# TestV1_0.net
KiCad netlist of a schematic drawn in EAGLE
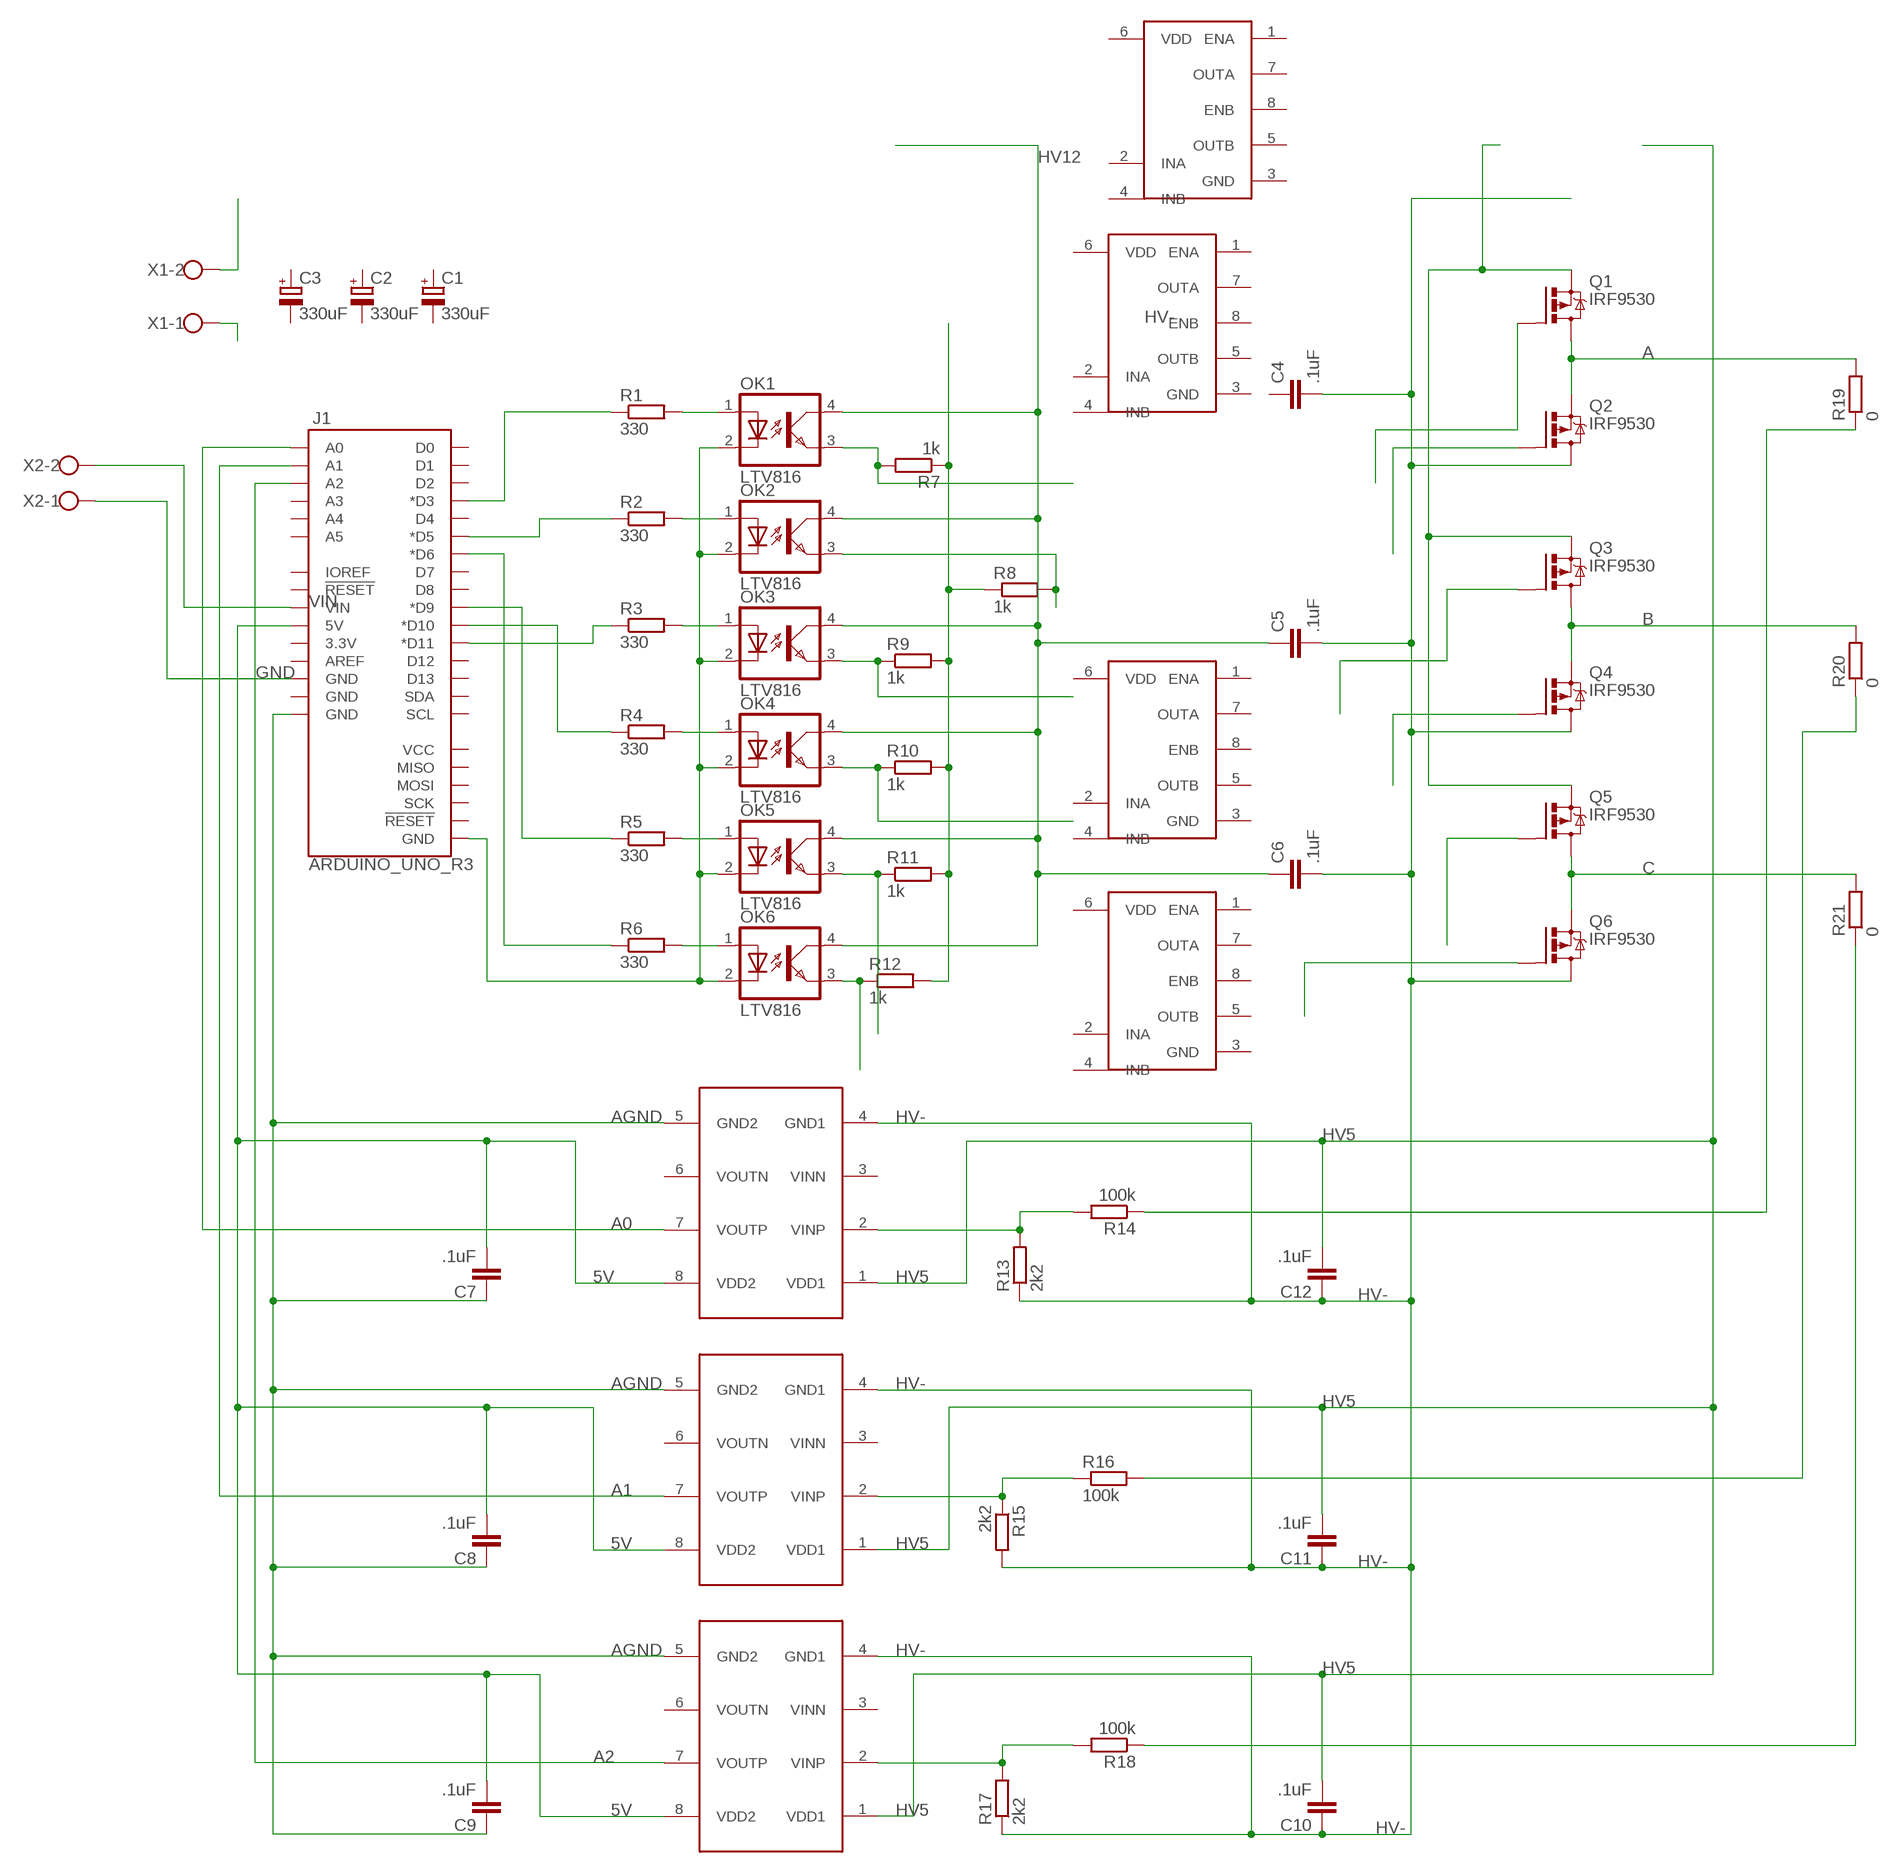
[diagram p0: schematic, sheet 1]

(export (version "E")
  (design (tool "Eeschema 10.0.6"))
  (components
    (comp (ref "C1")
      (value "330uF")
      (footprint "eagle-import:E5-13")
      (libsource (lib "eagle-import") (part "CPOL-EUE5-13"))
    )
    (comp (ref "C2")
      (value "330uF")
      (footprint "eagle-import:E5-13")
      (libsource (lib "eagle-import") (part "CPOL-EUE5-13"))
    )
    (comp (ref "C3")
      (value "330uF")
      (footprint "eagle-import:E5-13")
      (libsource (lib "eagle-import") (part "CPOL-EUE5-13"))
    )
    (comp (ref "C4")
      (value ".1uF")
      (footprint "eagle-import:C0603")
      (libsource (lib "eagle-import") (part "C-EUC0603"))
    )
    (comp (ref "C5")
      (value ".1uF")
      (footprint "eagle-import:C0603")
      (libsource (lib "eagle-import") (part "C-EUC0603"))
    )
    (comp (ref "C6")
      (value ".1uF")
      (footprint "eagle-import:C0603")
      (libsource (lib "eagle-import") (part "C-EUC0603"))
    )
    (comp (ref "C7")
      (value ".1uF")
      (footprint "eagle-import:C0603")
      (libsource (lib "eagle-import") (part "C-EUC0603"))
    )
    (comp (ref "C8")
      (value ".1uF")
      (footprint "eagle-import:C0603")
      (libsource (lib "eagle-import") (part "C-EUC0603"))
    )
    (comp (ref "C9")
      (value ".1uF")
      (footprint "eagle-import:C0603")
      (libsource (lib "eagle-import") (part "C-EUC0603"))
    )
    (comp (ref "C10")
      (value ".1uF")
      (footprint "eagle-import:C0603")
      (libsource (lib "eagle-import") (part "C-EUC0603"))
    )
    (comp (ref "C11")
      (value ".1uF")
      (footprint "eagle-import:C0603")
      (libsource (lib "eagle-import") (part "C-EUC0603"))
    )
    (comp (ref "C12")
      (value ".1uF")
      (footprint "eagle-import:C0603")
      (libsource (lib "eagle-import") (part "C-EUC0603"))
    )
    (comp (ref "J1")
      (value "ARDUINO_UNO_R3")
      (footprint "eagle-import:ARDUINO_R3")
      (libsource (lib "eagle-import") (part "ARDUINO_UNO_R3"))
    )
    (comp (ref "MAX17604_A")
      (value "MAX17604")
      (footprint "eagle-import:SO08")
      (libsource (lib "eagle-import") (part "MAX17604"))
    )
    (comp (ref "MAX17604_B")
      (value "MAX17604")
      (footprint "eagle-import:SO08")
      (libsource (lib "eagle-import") (part "MAX17604"))
    )
    (comp (ref "MAX17604_C")
      (value "MAX17604")
      (footprint "eagle-import:SO08")
      (libsource (lib "eagle-import") (part "MAX17604"))
    )
    (comp (ref "MAX17604_D")
      (value "MAX17604")
      (footprint "eagle-import:SO08")
      (libsource (lib "eagle-import") (part "MAX17604"))
    )
    (comp (ref "OK1")
      (value "LTV816")
      (footprint "eagle-import:DIL04")
      (libsource (lib "eagle-import") (part "LTV816"))
    )
    (comp (ref "OK2")
      (value "LTV816")
      (footprint "eagle-import:DIL04")
      (libsource (lib "eagle-import") (part "LTV816"))
    )
    (comp (ref "OK3")
      (value "LTV816")
      (footprint "eagle-import:DIL04")
      (libsource (lib "eagle-import") (part "LTV816"))
    )
    (comp (ref "OK4")
      (value "LTV816")
      (footprint "eagle-import:DIL04")
      (libsource (lib "eagle-import") (part "LTV816"))
    )
    (comp (ref "OK5")
      (value "LTV816")
      (footprint "eagle-import:DIL04")
      (libsource (lib "eagle-import") (part "LTV816"))
    )
    (comp (ref "OK6")
      (value "LTV816")
      (footprint "eagle-import:DIL04")
      (libsource (lib "eagle-import") (part "LTV816"))
    )
    (comp (ref "Q1")
      (value "IRF9530")
      (footprint "eagle-import:TO220BV")
      (libsource (lib "eagle-import") (part "IRF9530"))
    )
    (comp (ref "Q2")
      (value "IRF9530")
      (footprint "eagle-import:TO220BV")
      (libsource (lib "eagle-import") (part "IRF9530"))
    )
    (comp (ref "Q3")
      (value "IRF9530")
      (footprint "eagle-import:TO220BV")
      (libsource (lib "eagle-import") (part "IRF9530"))
    )
    (comp (ref "Q4")
      (value "IRF9530")
      (footprint "eagle-import:TO220BV")
      (libsource (lib "eagle-import") (part "IRF9530"))
    )
    (comp (ref "Q5")
      (value "IRF9530")
      (footprint "eagle-import:TO220BV")
      (libsource (lib "eagle-import") (part "IRF9530"))
    )
    (comp (ref "Q6")
      (value "IRF9530")
      (footprint "eagle-import:TO220BV")
      (libsource (lib "eagle-import") (part "IRF9530"))
    )
    (comp (ref "R1")
      (value "330")
      (footprint "eagle-import:R0603")
      (libsource (lib "eagle-import") (part "eagle-ltspice_217_RR0603"))
    )
    (comp (ref "R2")
      (value "330")
      (footprint "eagle-import:R0603")
      (libsource (lib "eagle-import") (part "eagle-ltspice_217_RR0603"))
    )
    (comp (ref "R3")
      (value "330")
      (footprint "eagle-import:R0603")
      (libsource (lib "eagle-import") (part "eagle-ltspice_217_RR0603"))
    )
    (comp (ref "R4")
      (value "330")
      (footprint "eagle-import:R0603")
      (libsource (lib "eagle-import") (part "eagle-ltspice_217_RR0603"))
    )
    (comp (ref "R5")
      (value "330")
      (footprint "eagle-import:R0603")
      (libsource (lib "eagle-import") (part "eagle-ltspice_217_RR0603"))
    )
    (comp (ref "R6")
      (value "330")
      (footprint "eagle-import:R0603")
      (libsource (lib "eagle-import") (part "eagle-ltspice_217_RR0603"))
    )
    (comp (ref "R7")
      (value "1k")
      (footprint "eagle-import:R0603")
      (libsource (lib "eagle-import") (part "eagle-ltspice_217_RR0603"))
    )
    (comp (ref "R8")
      (value "1k")
      (footprint "eagle-import:R0603")
      (libsource (lib "eagle-import") (part "eagle-ltspice_217_RR0603"))
    )
    (comp (ref "R9")
      (value "1k")
      (footprint "eagle-import:R0603")
      (libsource (lib "eagle-import") (part "eagle-ltspice_217_RR0603"))
    )
    (comp (ref "R10")
      (value "1k")
      (footprint "eagle-import:R0603")
      (libsource (lib "eagle-import") (part "eagle-ltspice_217_RR0603"))
    )
    (comp (ref "R11")
      (value "1k")
      (footprint "eagle-import:R0603")
      (libsource (lib "eagle-import") (part "eagle-ltspice_217_RR0603"))
    )
    (comp (ref "R12")
      (value "1k")
      (footprint "eagle-import:R0603")
      (libsource (lib "eagle-import") (part "eagle-ltspice_217_RR0603"))
    )
    (comp (ref "R13")
      (value "2k2")
      (footprint "eagle-import:R0603")
      (libsource (lib "eagle-import") (part "eagle-ltspice_217_RR0603"))
    )
    (comp (ref "R14")
      (value "100k")
      (footprint "eagle-import:R0603")
      (libsource (lib "eagle-import") (part "eagle-ltspice_217_RR0603"))
    )
    (comp (ref "R15")
      (value "2k2")
      (footprint "eagle-import:R0603")
      (libsource (lib "eagle-import") (part "eagle-ltspice_217_RR0603"))
    )
    (comp (ref "R16")
      (value "100k")
      (footprint "eagle-import:R0603")
      (libsource (lib "eagle-import") (part "eagle-ltspice_217_RR0603"))
    )
    (comp (ref "R17")
      (value "2k2")
      (footprint "eagle-import:R0603")
      (libsource (lib "eagle-import") (part "eagle-ltspice_217_RR0603"))
    )
    (comp (ref "R18")
      (value "100k")
      (footprint "eagle-import:R0603")
      (libsource (lib "eagle-import") (part "eagle-ltspice_217_RR0603"))
    )
    (comp (ref "R19")
      (value "0")
      (footprint "eagle-import:R0603")
      (libsource (lib "eagle-import") (part "RR0603"))
    )
    (comp (ref "R20")
      (value "0")
      (footprint "eagle-import:R0603")
      (libsource (lib "eagle-import") (part "RR0603"))
    )
    (comp (ref "R21")
      (value "0")
      (footprint "eagle-import:R0603")
      (libsource (lib "eagle-import") (part "RR0603"))
    )
    (comp (ref "U$7")
      (value "AMC1200")
      (footprint "eagle-import:SO08")
      (libsource (lib "eagle-import") (part "AMC1200"))
    )
    (comp (ref "U$8")
      (value "AMC1200")
      (footprint "eagle-import:SO08")
      (libsource (lib "eagle-import") (part "AMC1200"))
    )
    (comp (ref "U$9")
      (value "AMC1200")
      (footprint "eagle-import:SO08")
      (libsource (lib "eagle-import") (part "AMC1200"))
    )
    (comp (ref "X1")
      (value "SCREWCONNECTOR")
      (footprint "eagle-import:2PIN-SCREW-TERMINAL")
      (fields (field (name "MPN") "237-102"))
      (libsource (lib "eagle-import") (part "SCREWCONNECTOR"))
    )
    (comp (ref "X2")
      (value "SCREWCONNECTOR")
      (footprint "eagle-import:2PIN-SCREW-TERMINAL")
      (fields (field (name "MPN") "237-102"))
      (libsource (lib "eagle-import") (part "SCREWCONNECTOR"))
    )
  )
  (nets
    (net (code "1") (name "/5V") (class "Default")
      (node (ref "C7") (pin "2") (pinfunction "2_2") (pintype "passive"))
      (node (ref "C8") (pin "2") (pinfunction "2_2") (pintype "passive"))
      (node (ref "C9") (pin "2") (pinfunction "2_2") (pintype "passive"))
      (node (ref "J1") (pin "5V") (pinfunction "5V_5V") (pintype "bidirectional"))
      (node (ref "U$7") (pin "8") (pinfunction "VDD2_8") (pintype "bidirectional"))
      (node (ref "U$8") (pin "8") (pinfunction "VDD2_8") (pintype "bidirectional"))
      (node (ref "U$9") (pin "8") (pinfunction "VDD2_8") (pintype "bidirectional"))
    )
    (net (code "2") (name "/A") (class "Default")
      (node (ref "Q1") (pin "D") (pinfunction "D_D") (pintype "passive"))
      (node (ref "Q2") (pin "S") (pinfunction "S_S") (pintype "passive"))
      (node (ref "R19") (pin "2") (pinfunction "2_2") (pintype "passive"))
    )
    (net (code "3") (name "/A0") (class "Default")
      (node (ref "J1") (pin "A0") (pinfunction "A0_A0") (pintype "bidirectional"))
      (node (ref "U$7") (pin "7") (pinfunction "VOUTP_7") (pintype "bidirectional"))
    )
    (net (code "4") (name "/A1") (class "Default")
      (node (ref "J1") (pin "A1") (pinfunction "A1_A1") (pintype "bidirectional"))
      (node (ref "U$8") (pin "7") (pinfunction "VOUTP_7") (pintype "bidirectional"))
    )
    (net (code "5") (name "/A2") (class "Default")
      (node (ref "J1") (pin "A2") (pinfunction "A2_A2") (pintype "bidirectional"))
      (node (ref "U$9") (pin "7") (pinfunction "VOUTP_7") (pintype "bidirectional"))
    )
    (net (code "6") (name "/AGND") (class "Default")
      (node (ref "C7") (pin "1") (pinfunction "1_1") (pintype "passive"))
      (node (ref "C8") (pin "1") (pinfunction "1_1") (pintype "passive"))
      (node (ref "C9") (pin "1") (pinfunction "1_1") (pintype "passive"))
      (node (ref "J1") (pin "GND@2") (pinfunction "GND_GND@2") (pintype "bidirectional"))
      (node (ref "U$7") (pin "5") (pinfunction "GND2_5") (pintype "bidirectional"))
      (node (ref "U$8") (pin "5") (pinfunction "GND2_5") (pintype "bidirectional"))
      (node (ref "U$9") (pin "5") (pinfunction "GND2_5") (pintype "bidirectional"))
    )
    (net (code "7") (name "/B") (class "Default")
      (node (ref "Q3") (pin "D") (pinfunction "D_D") (pintype "passive"))
      (node (ref "Q4") (pin "S") (pinfunction "S_S") (pintype "passive"))
      (node (ref "R20") (pin "2") (pinfunction "2_2") (pintype "passive"))
    )
    (net (code "8") (name "/C") (class "Default")
      (node (ref "Q5") (pin "D") (pinfunction "D_D") (pintype "passive"))
      (node (ref "Q6") (pin "S") (pinfunction "S_S") (pintype "passive"))
      (node (ref "R21") (pin "2") (pinfunction "2_2") (pintype "passive"))
    )
    (net (code "9") (name "/GND") (class "Default")
      (node (ref "J1") (pin "GND@4") (pinfunction "GND_GND@4") (pintype "bidirectional"))
      (node (ref "X2") (pin "1") (pinfunction "KL_1") (pintype "passive"))
    )
    (net (code "10") (name "/HV-") (class "Default")
      (node (ref "C10") (pin "1") (pinfunction "1_1") (pintype "passive"))
      (node (ref "C11") (pin "1") (pinfunction "1_1") (pintype "passive"))
      (node (ref "C12") (pin "1") (pinfunction "1_1") (pintype "passive"))
      (node (ref "C4") (pin "2") (pinfunction "2_2") (pintype "passive"))
      (node (ref "C5") (pin "2") (pinfunction "2_2") (pintype "passive"))
      (node (ref "C6") (pin "2") (pinfunction "2_2") (pintype "passive"))
      (node (ref "Q2") (pin "D") (pinfunction "D_D") (pintype "passive"))
      (node (ref "Q4") (pin "D") (pinfunction "D_D") (pintype "passive"))
      (node (ref "Q6") (pin "D") (pinfunction "D_D") (pintype "passive"))
      (node (ref "R13") (pin "1") (pinfunction "1_1") (pintype "passive"))
      (node (ref "R15") (pin "2") (pinfunction "2_2") (pintype "passive"))
      (node (ref "R17") (pin "1") (pinfunction "1_1") (pintype "passive"))
      (node (ref "U$7") (pin "4") (pinfunction "GND1_4") (pintype "bidirectional"))
      (node (ref "U$8") (pin "4") (pinfunction "GND1_4") (pintype "bidirectional"))
      (node (ref "U$9") (pin "4") (pinfunction "GND1_4") (pintype "bidirectional"))
    )
    (net (code "11") (name "/HV5") (class "Default")
      (node (ref "C10") (pin "2") (pinfunction "2_2") (pintype "passive"))
      (node (ref "C11") (pin "2") (pinfunction "2_2") (pintype "passive"))
      (node (ref "C12") (pin "2") (pinfunction "2_2") (pintype "passive"))
      (node (ref "U$7") (pin "1") (pinfunction "VDD1_1") (pintype "bidirectional"))
      (node (ref "U$8") (pin "1") (pinfunction "VDD1_1") (pintype "bidirectional"))
      (node (ref "U$9") (pin "1") (pinfunction "VDD1_1") (pintype "bidirectional"))
    )
    (net (code "12") (name "/HV12") (class "Default")
      (node (ref "C5") (pin "1") (pinfunction "1_1") (pintype "passive"))
      (node (ref "C6") (pin "1") (pinfunction "1_1") (pintype "passive"))
      (node (ref "OK1") (pin "4") (pinfunction "COL_4") (pintype "passive"))
      (node (ref "OK2") (pin "4") (pinfunction "COL_4") (pintype "passive"))
      (node (ref "OK3") (pin "4") (pinfunction "COL_4") (pintype "passive"))
      (node (ref "OK4") (pin "4") (pinfunction "COL_4") (pintype "passive"))
      (node (ref "OK5") (pin "4") (pinfunction "COL_4") (pintype "passive"))
      (node (ref "OK6") (pin "4") (pinfunction "COL_4") (pintype "passive"))
    )
    (net (code "13") (name "/VIN") (class "Default")
      (node (ref "J1") (pin "VIN") (pinfunction "VIN_VIN") (pintype "bidirectional"))
      (node (ref "X2") (pin "2") (pinfunction "KL_2") (pintype "passive"))
    )
    (net (code "14") (name "Net-(J1-*D3)") (class "Default")
      (node (ref "J1") (pin "D3") (pinfunction "*D3_D3") (pintype "bidirectional"))
      (node (ref "R1") (pin "1") (pinfunction "1_1") (pintype "passive"))
    )
    (net (code "15") (name "Net-(J1-*D5)") (class "Default")
      (node (ref "J1") (pin "D5") (pinfunction "*D5_D5") (pintype "bidirectional"))
      (node (ref "R2") (pin "1") (pinfunction "1_1") (pintype "passive"))
    )
    (net (code "16") (name "Net-(J1-*D6)") (class "Default")
      (node (ref "J1") (pin "D6") (pinfunction "*D6_D6") (pintype "bidirectional"))
      (node (ref "R6") (pin "1") (pinfunction "1_1") (pintype "passive"))
    )
    (net (code "17") (name "Net-(J1-*D9)") (class "Default")
      (node (ref "J1") (pin "D9") (pinfunction "*D9_D9") (pintype "bidirectional"))
      (node (ref "R5") (pin "1") (pinfunction "1_1") (pintype "passive"))
    )
    (net (code "18") (name "Net-(J1-*D10)") (class "Default")
      (node (ref "J1") (pin "D10") (pinfunction "*D10_D10") (pintype "bidirectional"))
      (node (ref "R4") (pin "1") (pinfunction "1_1") (pintype "passive"))
    )
    (net (code "19") (name "Net-(J1-*D11)") (class "Default")
      (node (ref "J1") (pin "D11") (pinfunction "*D11_D11") (pintype "bidirectional"))
      (node (ref "R3") (pin "1") (pinfunction "1_1") (pintype "passive"))
    )
    (net (code "20") (name "Net-(OK1-A)") (class "Default")
      (node (ref "OK1") (pin "1") (pinfunction "A_1") (pintype "passive"))
      (node (ref "R1") (pin "2") (pinfunction "2_2") (pintype "passive"))
    )
    (net (code "21") (name "Net-(OK1-C)") (class "Default")
      (node (ref "J1") (pin "GND@1") (pinfunction "GND_GND@1") (pintype "bidirectional"))
      (node (ref "OK1") (pin "2") (pinfunction "C_2") (pintype "passive"))
      (node (ref "OK2") (pin "2") (pinfunction "C_2") (pintype "passive"))
      (node (ref "OK3") (pin "2") (pinfunction "C_2") (pintype "passive"))
      (node (ref "OK4") (pin "2") (pinfunction "C_2") (pintype "passive"))
      (node (ref "OK5") (pin "2") (pinfunction "C_2") (pintype "passive"))
      (node (ref "OK6") (pin "2") (pinfunction "C_2") (pintype "passive"))
    )
    (net (code "22") (name "Net-(OK1-EMIT)") (class "Default")
      (node (ref "OK1") (pin "3") (pinfunction "EMIT_3") (pintype "passive"))
      (node (ref "R7") (pin "2") (pinfunction "2_2") (pintype "passive"))
    )
    (net (code "23") (name "Net-(OK2-A)") (class "Default")
      (node (ref "OK2") (pin "1") (pinfunction "A_1") (pintype "passive"))
      (node (ref "R2") (pin "2") (pinfunction "2_2") (pintype "passive"))
    )
    (net (code "24") (name "Net-(OK2-EMIT)") (class "Default")
      (node (ref "OK2") (pin "3") (pinfunction "EMIT_3") (pintype "passive"))
      (node (ref "R8") (pin "2") (pinfunction "2_2") (pintype "passive"))
    )
    (net (code "25") (name "Net-(OK3-A)") (class "Default")
      (node (ref "OK3") (pin "1") (pinfunction "A_1") (pintype "passive"))
      (node (ref "R3") (pin "2") (pinfunction "2_2") (pintype "passive"))
    )
    (net (code "26") (name "Net-(OK3-EMIT)") (class "Default")
      (node (ref "OK3") (pin "3") (pinfunction "EMIT_3") (pintype "passive"))
      (node (ref "R9") (pin "1") (pinfunction "1_1") (pintype "passive"))
    )
    (net (code "27") (name "Net-(OK4-A)") (class "Default")
      (node (ref "OK4") (pin "1") (pinfunction "A_1") (pintype "passive"))
      (node (ref "R4") (pin "2") (pinfunction "2_2") (pintype "passive"))
    )
    (net (code "28") (name "Net-(OK4-EMIT)") (class "Default")
      (node (ref "OK4") (pin "3") (pinfunction "EMIT_3") (pintype "passive"))
      (node (ref "R10") (pin "1") (pinfunction "1_1") (pintype "passive"))
    )
    (net (code "29") (name "Net-(OK5-A)") (class "Default")
      (node (ref "OK5") (pin "1") (pinfunction "A_1") (pintype "passive"))
      (node (ref "R5") (pin "2") (pinfunction "2_2") (pintype "passive"))
    )
    (net (code "30") (name "Net-(OK5-EMIT)") (class "Default")
      (node (ref "OK5") (pin "3") (pinfunction "EMIT_3") (pintype "passive"))
      (node (ref "R11") (pin "1") (pinfunction "1_1") (pintype "passive"))
    )
    (net (code "31") (name "Net-(OK6-A)") (class "Default")
      (node (ref "OK6") (pin "1") (pinfunction "A_1") (pintype "passive"))
      (node (ref "R6") (pin "2") (pinfunction "2_2") (pintype "passive"))
    )
    (net (code "32") (name "Net-(OK6-EMIT)") (class "Default")
      (node (ref "OK6") (pin "3") (pinfunction "EMIT_3") (pintype "passive"))
      (node (ref "R12") (pin "1") (pinfunction "1_1") (pintype "passive"))
    )
    (net (code "33") (name "Net-(Q1-PadS)") (class "Default")
      (node (ref "Q1") (pin "S") (pinfunction "S_S") (pintype "passive"))
      (node (ref "Q3") (pin "S") (pinfunction "S_S") (pintype "passive"))
      (node (ref "Q5") (pin "S") (pinfunction "S_S") (pintype "passive"))
    )
    (net (code "34") (name "Net-(R10-Pad2)") (class "Default")
      (node (ref "R10") (pin "2") (pinfunction "2_2") (pintype "passive"))
      (node (ref "R11") (pin "2") (pinfunction "2_2") (pintype "passive"))
      (node (ref "R12") (pin "2") (pinfunction "2_2") (pintype "passive"))
      (node (ref "R7") (pin "1") (pinfunction "1_1") (pintype "passive"))
      (node (ref "R8") (pin "1") (pinfunction "1_1") (pintype "passive"))
      (node (ref "R9") (pin "2") (pinfunction "2_2") (pintype "passive"))
    )
    (net (code "35") (name "Net-(R14-Pad1)") (class "Default")
      (node (ref "R14") (pin "1") (pinfunction "1_1") (pintype "passive"))
      (node (ref "R19") (pin "1") (pinfunction "1_1") (pintype "passive"))
    )
    (net (code "36") (name "Net-(R16-Pad2)") (class "Default")
      (node (ref "R16") (pin "2") (pinfunction "2_2") (pintype "passive"))
      (node (ref "R20") (pin "1") (pinfunction "1_1") (pintype "passive"))
    )
    (net (code "37") (name "Net-(R18-Pad1)") (class "Default")
      (node (ref "R18") (pin "1") (pinfunction "1_1") (pintype "passive"))
      (node (ref "R21") (pin "1") (pinfunction "1_1") (pintype "passive"))
    )
    (net (code "38") (name "Net-(U$7-VINP)") (class "Default")
      (node (ref "R13") (pin "2") (pinfunction "2_2") (pintype "passive"))
      (node (ref "R14") (pin "2") (pinfunction "2_2") (pintype "passive"))
      (node (ref "U$7") (pin "2") (pinfunction "VINP_2") (pintype "bidirectional"))
    )
    (net (code "39") (name "Net-(U$8-VINP)") (class "Default")
      (node (ref "R15") (pin "1") (pinfunction "1_1") (pintype "passive"))
      (node (ref "R16") (pin "1") (pinfunction "1_1") (pintype "passive"))
      (node (ref "U$8") (pin "2") (pinfunction "VINP_2") (pintype "bidirectional"))
    )
    (net (code "40") (name "Net-(U$9-VINP)") (class "Default")
      (node (ref "R17") (pin "2") (pinfunction "2_2") (pintype "passive"))
      (node (ref "R18") (pin "2") (pinfunction "2_2") (pintype "passive"))
      (node (ref "U$9") (pin "2") (pinfunction "VINP_2") (pintype "bidirectional"))
    )
    (net (code "41") (name "unconnected-(C1-Pad+)") (class "Default")
      (node (ref "C1") (pin "+") (pinfunction "+_+") (pintype "passive"))
    )
    (net (code "42") (name "unconnected-(C1-Pad-)") (class "Default")
      (node (ref "C1") (pin "-") (pinfunction "-_-") (pintype "passive"))
    )
    (net (code "43") (name "unconnected-(C2-Pad+)") (class "Default")
      (node (ref "C2") (pin "+") (pinfunction "+_+") (pintype "passive"))
    )
    (net (code "44") (name "unconnected-(C2-Pad-)") (class "Default")
      (node (ref "C2") (pin "-") (pinfunction "-_-") (pintype "passive"))
    )
    (net (code "45") (name "unconnected-(C3-Pad+)") (class "Default")
      (node (ref "C3") (pin "+") (pinfunction "+_+") (pintype "passive"))
    )
    (net (code "46") (name "unconnected-(C3-Pad-)") (class "Default")
      (node (ref "C3") (pin "-") (pinfunction "-_-") (pintype "passive"))
    )
    (net (code "47") (name "unconnected-(C4-Pad1)") (class "Default")
      (node (ref "C4") (pin "1") (pinfunction "1_1") (pintype "passive"))
    )
    (net (code "48") (name "unconnected-(J1-GND-PadGND@3)") (class "Default")
      (node (ref "J1") (pin "GND@3") (pinfunction "GND_GND@3") (pintype "bidirectional"))
    )
    (net (code "49") (name "unconnected-(J1-Pad3.3V)") (class "Default")
      (node (ref "J1") (pin "3.3V") (pinfunction "3.3V_3.3V") (pintype "bidirectional"))
    )
    (net (code "50") (name "unconnected-(J1-PadA3)") (class "Default")
      (node (ref "J1") (pin "A3") (pinfunction "A3_A3") (pintype "bidirectional"))
    )
    (net (code "51") (name "unconnected-(J1-PadA4)") (class "Default")
      (node (ref "J1") (pin "A4") (pinfunction "A4_A4") (pintype "bidirectional"))
    )
    (net (code "52") (name "unconnected-(J1-PadA5)") (class "Default")
      (node (ref "J1") (pin "A5") (pinfunction "A5_A5") (pintype "bidirectional"))
    )
    (net (code "53") (name "unconnected-(J1-PadAREF)") (class "Default")
      (node (ref "J1") (pin "AREF") (pinfunction "AREF_AREF") (pintype "bidirectional"))
    )
    (net (code "54") (name "unconnected-(J1-PadD0)") (class "Default")
      (node (ref "J1") (pin "D0") (pinfunction "D0_D0") (pintype "bidirectional"))
    )
    (net (code "55") (name "unconnected-(J1-PadD1)") (class "Default")
      (node (ref "J1") (pin "D1") (pinfunction "D1_D1") (pintype "bidirectional"))
    )
    (net (code "56") (name "unconnected-(J1-PadD2)") (class "Default")
      (node (ref "J1") (pin "D2") (pinfunction "D2_D2") (pintype "bidirectional"))
    )
    (net (code "57") (name "unconnected-(J1-PadD4)") (class "Default")
      (node (ref "J1") (pin "D4") (pinfunction "D4_D4") (pintype "bidirectional"))
    )
    (net (code "58") (name "unconnected-(J1-PadD7)") (class "Default")
      (node (ref "J1") (pin "D7") (pinfunction "D7_D7") (pintype "bidirectional"))
    )
    (net (code "59") (name "unconnected-(J1-PadD8)") (class "Default")
      (node (ref "J1") (pin "D8") (pinfunction "D8_D8") (pintype "bidirectional"))
    )
    (net (code "60") (name "unconnected-(J1-PadD12)") (class "Default")
      (node (ref "J1") (pin "D12") (pinfunction "D12_D12") (pintype "bidirectional"))
    )
    (net (code "61") (name "unconnected-(J1-PadD13)") (class "Default")
      (node (ref "J1") (pin "D13") (pinfunction "D13_D13") (pintype "bidirectional"))
    )
    (net (code "62") (name "unconnected-(J1-PadIOREF)") (class "Default")
      (node (ref "J1") (pin "IOREF") (pinfunction "IOREF_IOREF") (pintype "bidirectional"))
    )
    (net (code "63") (name "unconnected-(J1-PadMISO)") (class "Default")
      (node (ref "J1") (pin "MISO") (pinfunction "MISO_MISO") (pintype "bidirectional"))
    )
    (net (code "64") (name "unconnected-(J1-PadMOSI)") (class "Default")
      (node (ref "J1") (pin "MOSI") (pinfunction "MOSI_MOSI") (pintype "bidirectional"))
    )
    (net (code "65") (name "unconnected-(J1-PadSCK)") (class "Default")
      (node (ref "J1") (pin "SCK") (pinfunction "SCK_SCK") (pintype "bidirectional"))
    )
    (net (code "66") (name "unconnected-(J1-PadSCL)") (class "Default")
      (node (ref "J1") (pin "SCL") (pinfunction "SCL_SCL") (pintype "bidirectional"))
    )
    (net (code "67") (name "unconnected-(J1-PadSDA)") (class "Default")
      (node (ref "J1") (pin "SDA") (pinfunction "SDA_SDA") (pintype "bidirectional"))
    )
    (net (code "68") (name "unconnected-(J1-PadVCC)") (class "Default")
      (node (ref "J1") (pin "VCC") (pinfunction "VCC_VCC") (pintype "bidirectional"))
    )
    (net (code "69") (name "unconnected-(J1-~{RESET}-PadRESET@1)") (class "Default")
      (node (ref "J1") (pin "RESET@1") (pinfunction "~{RESET}_RESET@1") (pintype "bidirectional"))
    )
    (net (code "70") (name "unconnected-(J1-~{RESET}-PadRESET@2)") (class "Default")
      (node (ref "J1") (pin "RESET@2") (pinfunction "~{RESET}_RESET@2") (pintype "bidirectional"))
    )
    (net (code "71") (name "unconnected-(MAX17604_A-ENA-Pad1)") (class "Default")
      (node (ref "MAX17604_A") (pin "1") (pinfunction "ENA_1") (pintype "bidirectional"))
    )
    (net (code "72") (name "unconnected-(MAX17604_A-ENB-Pad8)") (class "Default")
      (node (ref "MAX17604_A") (pin "8") (pinfunction "ENB_8") (pintype "bidirectional"))
    )
    (net (code "73") (name "unconnected-(MAX17604_A-GND-Pad3)") (class "Default")
      (node (ref "MAX17604_A") (pin "3") (pinfunction "GND_3") (pintype "bidirectional"))
    )
    (net (code "74") (name "unconnected-(MAX17604_A-INA-Pad2)") (class "Default")
      (node (ref "MAX17604_A") (pin "2") (pinfunction "INA_2") (pintype "bidirectional"))
    )
    (net (code "75") (name "unconnected-(MAX17604_A-INB-Pad4)") (class "Default")
      (node (ref "MAX17604_A") (pin "4") (pinfunction "INB_4") (pintype "bidirectional"))
    )
    (net (code "76") (name "unconnected-(MAX17604_A-OUTA-Pad7)") (class "Default")
      (node (ref "MAX17604_A") (pin "7") (pinfunction "OUTA_7") (pintype "bidirectional"))
    )
    (net (code "77") (name "unconnected-(MAX17604_A-OUTB-Pad5)") (class "Default")
      (node (ref "MAX17604_A") (pin "5") (pinfunction "OUTB_5") (pintype "bidirectional"))
    )
    (net (code "78") (name "unconnected-(MAX17604_A-VDD-Pad6)") (class "Default")
      (node (ref "MAX17604_A") (pin "6") (pinfunction "VDD_6") (pintype "bidirectional"))
    )
    (net (code "79") (name "unconnected-(MAX17604_B-ENA-Pad1)") (class "Default")
      (node (ref "MAX17604_B") (pin "1") (pinfunction "ENA_1") (pintype "bidirectional"))
    )
    (net (code "80") (name "unconnected-(MAX17604_B-ENB-Pad8)") (class "Default")
      (node (ref "MAX17604_B") (pin "8") (pinfunction "ENB_8") (pintype "bidirectional"))
    )
    (net (code "81") (name "unconnected-(MAX17604_B-GND-Pad3)") (class "Default")
      (node (ref "MAX17604_B") (pin "3") (pinfunction "GND_3") (pintype "bidirectional"))
    )
    (net (code "82") (name "unconnected-(MAX17604_B-INA-Pad2)") (class "Default")
      (node (ref "MAX17604_B") (pin "2") (pinfunction "INA_2") (pintype "bidirectional"))
    )
    (net (code "83") (name "unconnected-(MAX17604_B-INB-Pad4)") (class "Default")
      (node (ref "MAX17604_B") (pin "4") (pinfunction "INB_4") (pintype "bidirectional"))
    )
    (net (code "84") (name "unconnected-(MAX17604_B-OUTA-Pad7)") (class "Default")
      (node (ref "MAX17604_B") (pin "7") (pinfunction "OUTA_7") (pintype "bidirectional"))
    )
    (net (code "85") (name "unconnected-(MAX17604_B-OUTB-Pad5)") (class "Default")
      (node (ref "MAX17604_B") (pin "5") (pinfunction "OUTB_5") (pintype "bidirectional"))
    )
    (net (code "86") (name "unconnected-(MAX17604_B-VDD-Pad6)") (class "Default")
      (node (ref "MAX17604_B") (pin "6") (pinfunction "VDD_6") (pintype "bidirectional"))
    )
    (net (code "87") (name "unconnected-(MAX17604_C-ENA-Pad1)") (class "Default")
      (node (ref "MAX17604_C") (pin "1") (pinfunction "ENA_1") (pintype "bidirectional"))
    )
    (net (code "88") (name "unconnected-(MAX17604_C-ENB-Pad8)") (class "Default")
      (node (ref "MAX17604_C") (pin "8") (pinfunction "ENB_8") (pintype "bidirectional"))
    )
    (net (code "89") (name "unconnected-(MAX17604_C-GND-Pad3)") (class "Default")
      (node (ref "MAX17604_C") (pin "3") (pinfunction "GND_3") (pintype "bidirectional"))
    )
    (net (code "90") (name "unconnected-(MAX17604_C-INA-Pad2)") (class "Default")
      (node (ref "MAX17604_C") (pin "2") (pinfunction "INA_2") (pintype "bidirectional"))
    )
    (net (code "91") (name "unconnected-(MAX17604_C-INB-Pad4)") (class "Default")
      (node (ref "MAX17604_C") (pin "4") (pinfunction "INB_4") (pintype "bidirectional"))
    )
    (net (code "92") (name "unconnected-(MAX17604_C-OUTA-Pad7)") (class "Default")
      (node (ref "MAX17604_C") (pin "7") (pinfunction "OUTA_7") (pintype "bidirectional"))
    )
    (net (code "93") (name "unconnected-(MAX17604_C-OUTB-Pad5)") (class "Default")
      (node (ref "MAX17604_C") (pin "5") (pinfunction "OUTB_5") (pintype "bidirectional"))
    )
    (net (code "94") (name "unconnected-(MAX17604_C-VDD-Pad6)") (class "Default")
      (node (ref "MAX17604_C") (pin "6") (pinfunction "VDD_6") (pintype "bidirectional"))
    )
    (net (code "95") (name "unconnected-(MAX17604_D-ENA-Pad1)") (class "Default")
      (node (ref "MAX17604_D") (pin "1") (pinfunction "ENA_1") (pintype "bidirectional"))
    )
    (net (code "96") (name "unconnected-(MAX17604_D-ENB-Pad8)") (class "Default")
      (node (ref "MAX17604_D") (pin "8") (pinfunction "ENB_8") (pintype "bidirectional"))
    )
    (net (code "97") (name "unconnected-(MAX17604_D-GND-Pad3)") (class "Default")
      (node (ref "MAX17604_D") (pin "3") (pinfunction "GND_3") (pintype "bidirectional"))
    )
    (net (code "98") (name "unconnected-(MAX17604_D-INA-Pad2)") (class "Default")
      (node (ref "MAX17604_D") (pin "2") (pinfunction "INA_2") (pintype "bidirectional"))
    )
    (net (code "99") (name "unconnected-(MAX17604_D-INB-Pad4)") (class "Default")
      (node (ref "MAX17604_D") (pin "4") (pinfunction "INB_4") (pintype "bidirectional"))
    )
    (net (code "100") (name "unconnected-(MAX17604_D-OUTA-Pad7)") (class "Default")
      (node (ref "MAX17604_D") (pin "7") (pinfunction "OUTA_7") (pintype "bidirectional"))
    )
    (net (code "101") (name "unconnected-(MAX17604_D-OUTB-Pad5)") (class "Default")
      (node (ref "MAX17604_D") (pin "5") (pinfunction "OUTB_5") (pintype "bidirectional"))
    )
    (net (code "102") (name "unconnected-(MAX17604_D-VDD-Pad6)") (class "Default")
      (node (ref "MAX17604_D") (pin "6") (pinfunction "VDD_6") (pintype "bidirectional"))
    )
    (net (code "103") (name "unconnected-(Q1-PadG)") (class "Default")
      (node (ref "Q1") (pin "G") (pinfunction "G_G") (pintype "passive"))
    )
    (net (code "104") (name "unconnected-(Q2-PadG)") (class "Default")
      (node (ref "Q2") (pin "G") (pinfunction "G_G") (pintype "passive"))
    )
    (net (code "105") (name "unconnected-(Q3-PadG)") (class "Default")
      (node (ref "Q3") (pin "G") (pinfunction "G_G") (pintype "passive"))
    )
    (net (code "106") (name "unconnected-(Q4-PadG)") (class "Default")
      (node (ref "Q4") (pin "G") (pinfunction "G_G") (pintype "passive"))
    )
    (net (code "107") (name "unconnected-(Q5-PadG)") (class "Default")
      (node (ref "Q5") (pin "G") (pinfunction "G_G") (pintype "passive"))
    )
    (net (code "108") (name "unconnected-(Q6-PadG)") (class "Default")
      (node (ref "Q6") (pin "G") (pinfunction "G_G") (pintype "passive"))
    )
    (net (code "109") (name "unconnected-(U$7-VINN-Pad3)") (class "Default")
      (node (ref "U$7") (pin "3") (pinfunction "VINN_3") (pintype "bidirectional"))
    )
    (net (code "110") (name "unconnected-(U$7-VOUTN-Pad6)") (class "Default")
      (node (ref "U$7") (pin "6") (pinfunction "VOUTN_6") (pintype "bidirectional"))
    )
    (net (code "111") (name "unconnected-(U$8-VINN-Pad3)") (class "Default")
      (node (ref "U$8") (pin "3") (pinfunction "VINN_3") (pintype "bidirectional"))
    )
    (net (code "112") (name "unconnected-(U$8-VOUTN-Pad6)") (class "Default")
      (node (ref "U$8") (pin "6") (pinfunction "VOUTN_6") (pintype "bidirectional"))
    )
    (net (code "113") (name "unconnected-(U$9-VINN-Pad3)") (class "Default")
      (node (ref "U$9") (pin "3") (pinfunction "VINN_3") (pintype "bidirectional"))
    )
    (net (code "114") (name "unconnected-(U$9-VOUTN-Pad6)") (class "Default")
      (node (ref "U$9") (pin "6") (pinfunction "VOUTN_6") (pintype "bidirectional"))
    )
    (net (code "115") (name "unconnected-(X1A-KL-Pad1)") (class "Default")
      (node (ref "X1") (pin "1") (pinfunction "KL_1") (pintype "passive"))
    )
    (net (code "116") (name "unconnected-(X1B-KL-Pad2)") (class "Default")
      (node (ref "X1") (pin "2") (pinfunction "KL_2") (pintype "passive"))
    )
  )
)
